# top_level.net
KiCad netlist of a schematic drawn in Altium Designer
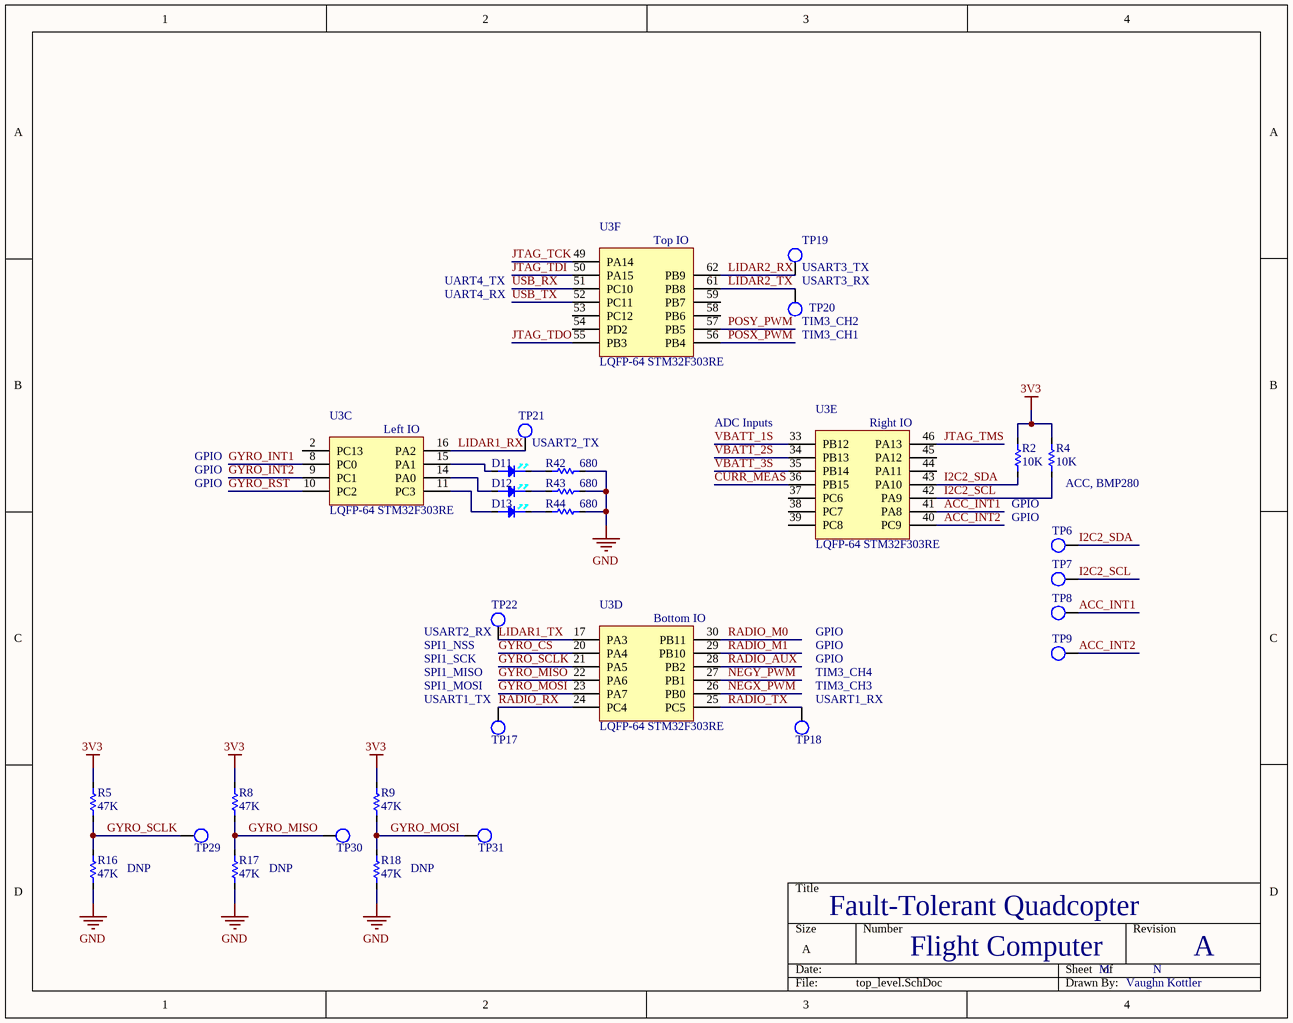
[diagram p0: top_level.SchDoc]

(export (version "E")
  (design (tool "Eeschema 10.0.6"))
  (components
    (comp (ref "D11")
      (value "LED-WHT-20mA")
      (footprint "LED-0805")
      (description "2.2V, 0805")
      (libsource (lib "passive") (part "LED-WHT-20mA"))
    )
    (comp (ref "D12")
      (value "LED-WHT-20mA")
      (footprint "LED-0805")
      (description "2.2V, 0805")
      (libsource (lib "passive") (part "LED-WHT-20mA"))
    )
    (comp (ref "D13")
      (value "LED-WHT-20mA")
      (footprint "LED-0805")
      (description "2.2V, 0805")
      (libsource (lib "passive") (part "LED-WHT-20mA"))
    )
    (comp (ref "R2")
      (value "10K")
      (footprint "RES-0805")
      (description "0805")
      (libsource (lib "passive") (part "RES-10K-1/8W"))
    )
    (comp (ref "R4")
      (value "10K")
      (footprint "RES-0805")
      (description "0805")
      (libsource (lib "passive") (part "RES-10K-1/8W"))
    )
    (comp (ref "R5")
      (value "47K")
      (footprint "RES-0805")
      (description "0805")
      (libsource (lib "passive") (part "RES-47K-1/8W"))
    )
    (comp (ref "R8")
      (value "47K")
      (footprint "RES-0805")
      (description "0805")
      (libsource (lib "passive") (part "RES-47K-1/8W"))
    )
    (comp (ref "R9")
      (value "47K")
      (footprint "RES-0805")
      (description "0805")
      (libsource (lib "passive") (part "RES-47K-1/8W"))
    )
    (comp (ref "R16")
      (value "47K")
      (footprint "RES-0805")
      (description "0805")
      (libsource (lib "passive") (part "RES-47K-1/8W"))
    )
    (comp (ref "R17")
      (value "47K")
      (footprint "RES-0805")
      (description "0805")
      (libsource (lib "passive") (part "RES-47K-1/8W"))
    )
    (comp (ref "R18")
      (value "47K")
      (footprint "RES-0805")
      (description "0805")
      (libsource (lib "passive") (part "RES-47K-1/8W"))
    )
    (comp (ref "R42")
      (value "680")
      (footprint "RES-0805")
      (description "0805")
      (libsource (lib "passive") (part "RES-680-1/8W"))
    )
    (comp (ref "R43")
      (value "680")
      (footprint "RES-0805")
      (description "0805")
      (libsource (lib "passive") (part "RES-680-1/8W"))
    )
    (comp (ref "R44")
      (value "680")
      (footprint "RES-0805")
      (description "0805")
      (libsource (lib "passive") (part "RES-680-1/8W"))
    )
    (comp (ref "TP6")
      (value "Test Point")
      (footprint "0603 Test Point")
      (description "0603")
      (libsource (lib "passive") (part "Test Point"))
    )
    (comp (ref "TP7")
      (value "Test Point")
      (footprint "0603 Test Point")
      (description "0603")
      (libsource (lib "passive") (part "Test Point"))
    )
    (comp (ref "TP8")
      (value "Test Point")
      (footprint "0603 Test Point")
      (description "0603")
      (libsource (lib "passive") (part "Test Point"))
    )
    (comp (ref "TP9")
      (value "Test Point")
      (footprint "0603 Test Point")
      (description "0603")
      (libsource (lib "passive") (part "Test Point"))
    )
    (comp (ref "TP17")
      (value "Test Point")
      (footprint "0603 Test Point")
      (description "0603")
      (libsource (lib "passive") (part "Test Point"))
    )
    (comp (ref "TP18")
      (value "Test Point")
      (footprint "0603 Test Point")
      (description "0603")
      (libsource (lib "passive") (part "Test Point"))
    )
    (comp (ref "TP19")
      (value "Test Point")
      (footprint "0603 Test Point")
      (description "0603")
      (libsource (lib "passive") (part "Test Point"))
    )
    (comp (ref "TP20")
      (value "Test Point")
      (footprint "0603 Test Point")
      (description "0603")
      (libsource (lib "passive") (part "Test Point"))
    )
    (comp (ref "TP21")
      (value "Test Point")
      (footprint "0603 Test Point")
      (description "0603")
      (libsource (lib "passive") (part "Test Point"))
    )
    (comp (ref "TP22")
      (value "Test Point")
      (footprint "0603 Test Point")
      (description "0603")
      (libsource (lib "passive") (part "Test Point"))
    )
    (comp (ref "TP29")
      (value "Test Point")
      (footprint "0603 Test Point")
      (description "0603")
      (libsource (lib "passive") (part "Test Point"))
    )
    (comp (ref "TP30")
      (value "Test Point")
      (footprint "0603 Test Point")
      (description "0603")
      (libsource (lib "passive") (part "Test Point"))
    )
    (comp (ref "TP31")
      (value "Test Point")
      (footprint "0603 Test Point")
      (description "0603")
      (libsource (lib "passive") (part "Test Point"))
    )
    (comp (ref "U3")
      (value "LQFP-64 STM32F303RE")
      (footprint "LQFP64")
      (description "ARM Cortex-M4 32-bit MCU+FPU")
      (libsource (lib "ic") (part "STM32F303RET6"))
    )
  )
  (nets
    (net (code "1") (name "/ACC_INT1") (class "Default")
      (node (ref "TP8") (pin "1") (pinfunction "1_1") (pintype "passive"))
      (node (ref "U3") (pin "41") (pinfunction "PA8_41") (pintype "passive"))
    )
    (net (code "2") (name "/ACC_INT2") (class "Default")
      (node (ref "TP9") (pin "1") (pinfunction "1_1") (pintype "passive"))
      (node (ref "U3") (pin "40") (pinfunction "PC9_40") (pintype "passive"))
    )
    (net (code "3") (name "/CURR_MEAS") (class "Default")
      (node (ref "U3") (pin "36") (pinfunction "PB15_36") (pintype "passive"))
    )
    (net (code "4") (name "/GYRO_CS") (class "Default")
      (node (ref "U3") (pin "20") (pinfunction "PA4_20") (pintype "passive"))
    )
    (net (code "5") (name "/GYRO_INT1") (class "Default")
      (node (ref "U3") (pin "8") (pinfunction "PC0_8") (pintype "passive"))
    )
    (net (code "6") (name "/GYRO_INT2") (class "Default")
      (node (ref "U3") (pin "9") (pinfunction "PC1_9") (pintype "passive"))
    )
    (net (code "7") (name "/GYRO_MISO") (class "Default")
      (node (ref "R17") (pin "2") (pinfunction "2_2") (pintype "passive"))
      (node (ref "R8") (pin "1") (pinfunction "1_1") (pintype "passive"))
      (node (ref "TP30") (pin "1") (pinfunction "1_1") (pintype "passive"))
      (node (ref "U3") (pin "22") (pinfunction "PA6_22") (pintype "passive"))
    )
    (net (code "8") (name "/GYRO_MOSI") (class "Default")
      (node (ref "R18") (pin "2") (pinfunction "2_2") (pintype "passive"))
      (node (ref "R9") (pin "1") (pinfunction "1_1") (pintype "passive"))
      (node (ref "TP31") (pin "1") (pinfunction "1_1") (pintype "passive"))
      (node (ref "U3") (pin "23") (pinfunction "PA7_23") (pintype "passive"))
    )
    (net (code "9") (name "/GYRO_RST") (class "Default")
      (node (ref "U3") (pin "10") (pinfunction "PC2_10") (pintype "passive"))
    )
    (net (code "10") (name "/GYRO_SCLK") (class "Default")
      (node (ref "R16") (pin "2") (pinfunction "2_2") (pintype "passive"))
      (node (ref "R5") (pin "1") (pinfunction "1_1") (pintype "passive"))
      (node (ref "TP29") (pin "1") (pinfunction "1_1") (pintype "passive"))
      (node (ref "U3") (pin "21") (pinfunction "PA5_21") (pintype "passive"))
    )
    (net (code "11") (name "/I2C2_SCL") (class "Default")
      (node (ref "R4") (pin "1") (pinfunction "1_1") (pintype "passive"))
      (node (ref "TP7") (pin "1") (pinfunction "1_1") (pintype "passive"))
      (node (ref "U3") (pin "42") (pinfunction "PA9_42") (pintype "passive"))
    )
    (net (code "12") (name "/I2C2_SDA") (class "Default")
      (node (ref "R2") (pin "1") (pinfunction "1_1") (pintype "passive"))
      (node (ref "TP6") (pin "1") (pinfunction "1_1") (pintype "passive"))
      (node (ref "U3") (pin "43") (pinfunction "PA10_43") (pintype "passive"))
    )
    (net (code "13") (name "/JTAG_TCK") (class "Default")
      (node (ref "U3") (pin "49") (pinfunction "PA14_49") (pintype "passive"))
    )
    (net (code "14") (name "/JTAG_TDI") (class "Default")
      (node (ref "U3") (pin "50") (pinfunction "PA15_50") (pintype "passive"))
    )
    (net (code "15") (name "/JTAG_TDO") (class "Default")
      (node (ref "U3") (pin "55") (pinfunction "PB3_55") (pintype "passive"))
    )
    (net (code "16") (name "/JTAG_TMS") (class "Default")
      (node (ref "U3") (pin "46") (pinfunction "PA13_46") (pintype "passive"))
    )
    (net (code "17") (name "/LIDAR1_RX") (class "Default")
      (node (ref "TP21") (pin "1") (pinfunction "1_1") (pintype "passive"))
      (node (ref "U3") (pin "16") (pinfunction "PA2_16") (pintype "passive"))
    )
    (net (code "18") (name "/LIDAR1_TX") (class "Default")
      (node (ref "TP22") (pin "1") (pinfunction "1_1") (pintype "passive"))
      (node (ref "U3") (pin "17") (pinfunction "PA3_17") (pintype "passive"))
    )
    (net (code "19") (name "/LIDAR2_RX") (class "Default")
      (node (ref "TP19") (pin "1") (pinfunction "1_1") (pintype "passive"))
      (node (ref "U3") (pin "62") (pinfunction "PB9_62") (pintype "passive"))
    )
    (net (code "20") (name "/LIDAR2_TX") (class "Default")
      (node (ref "TP20") (pin "1") (pinfunction "1_1") (pintype "passive"))
      (node (ref "U3") (pin "61") (pinfunction "PB8_61") (pintype "passive"))
    )
    (net (code "21") (name "/NEGX_PWM") (class "Default")
      (node (ref "U3") (pin "26") (pinfunction "PB0_26") (pintype "passive"))
    )
    (net (code "22") (name "/NEGY_PWM") (class "Default")
      (node (ref "U3") (pin "27") (pinfunction "PB1_27") (pintype "passive"))
    )
    (net (code "23") (name "/POSX_PWM") (class "Default")
      (node (ref "U3") (pin "56") (pinfunction "PB4_56") (pintype "passive"))
    )
    (net (code "24") (name "/POSY_PWM") (class "Default")
      (node (ref "U3") (pin "57") (pinfunction "PB5_57") (pintype "passive"))
    )
    (net (code "25") (name "/RADIO_AUX") (class "Default")
      (node (ref "U3") (pin "28") (pinfunction "PB2_28") (pintype "passive"))
    )
    (net (code "26") (name "/RADIO_M0") (class "Default")
      (node (ref "U3") (pin "30") (pinfunction "PB11_30") (pintype "passive"))
    )
    (net (code "27") (name "/RADIO_M1") (class "Default")
      (node (ref "U3") (pin "29") (pinfunction "PB10_29") (pintype "passive"))
    )
    (net (code "28") (name "/RADIO_RX") (class "Default")
      (node (ref "TP17") (pin "1") (pinfunction "1_1") (pintype "passive"))
      (node (ref "U3") (pin "24") (pinfunction "PC4_24") (pintype "passive"))
    )
    (net (code "29") (name "/RADIO_TX") (class "Default")
      (node (ref "TP18") (pin "1") (pinfunction "1_1") (pintype "passive"))
      (node (ref "U3") (pin "25") (pinfunction "PC5_25") (pintype "passive"))
    )
    (net (code "30") (name "/USB_RX") (class "Default")
      (node (ref "U3") (pin "51") (pinfunction "PC10_51") (pintype "passive"))
    )
    (net (code "31") (name "/USB_TX") (class "Default")
      (node (ref "U3") (pin "52") (pinfunction "PC11_52") (pintype "passive"))
    )
    (net (code "32") (name "/VBATT_1S") (class "Default")
      (node (ref "U3") (pin "33") (pinfunction "PB12_33") (pintype "passive"))
    )
    (net (code "33") (name "/VBATT_2S") (class "Default")
      (node (ref "U3") (pin "34") (pinfunction "PB13_34") (pintype "passive"))
    )
    (net (code "34") (name "/VBATT_3S") (class "Default")
      (node (ref "U3") (pin "35") (pinfunction "PB14_35") (pintype "passive"))
    )
    (net (code "35") (name "3V3") (class "Default")
      (node (ref "R2") (pin "2") (pinfunction "2_2") (pintype "passive"))
      (node (ref "R4") (pin "2") (pinfunction "2_2") (pintype "passive"))
      (node (ref "R5") (pin "2") (pinfunction "2_2") (pintype "passive"))
      (node (ref "R8") (pin "2") (pinfunction "2_2") (pintype "passive"))
      (node (ref "R9") (pin "2") (pinfunction "2_2") (pintype "passive"))
    )
    (net (code "36") (name "GND") (class "Default")
      (node (ref "R16") (pin "1") (pinfunction "1_1") (pintype "passive"))
      (node (ref "R17") (pin "1") (pinfunction "1_1") (pintype "passive"))
      (node (ref "R18") (pin "1") (pinfunction "1_1") (pintype "passive"))
      (node (ref "R42") (pin "2") (pinfunction "2_2") (pintype "passive"))
      (node (ref "R43") (pin "2") (pinfunction "2_2") (pintype "passive"))
      (node (ref "R44") (pin "2") (pinfunction "2_2") (pintype "passive"))
    )
    (net (code "37") (name "Net-(D11-AN)") (class "Default")
      (node (ref "D11") (pin "2") (pinfunction "AN_2") (pintype "passive"))
      (node (ref "R42") (pin "1") (pinfunction "1_1") (pintype "passive"))
    )
    (net (code "38") (name "Net-(D11-CT)") (class "Default")
      (node (ref "D11") (pin "1") (pinfunction "CT_1") (pintype "passive"))
      (node (ref "U3") (pin "15") (pinfunction "PA1_15") (pintype "passive"))
    )
    (net (code "39") (name "Net-(D12-AN)") (class "Default")
      (node (ref "D12") (pin "2") (pinfunction "AN_2") (pintype "passive"))
      (node (ref "R43") (pin "1") (pinfunction "1_1") (pintype "passive"))
    )
    (net (code "40") (name "Net-(D12-CT)") (class "Default")
      (node (ref "D12") (pin "1") (pinfunction "CT_1") (pintype "passive"))
      (node (ref "U3") (pin "14") (pinfunction "PA0_14") (pintype "passive"))
    )
    (net (code "41") (name "Net-(D13-AN)") (class "Default")
      (node (ref "D13") (pin "2") (pinfunction "AN_2") (pintype "passive"))
      (node (ref "R44") (pin "1") (pinfunction "1_1") (pintype "passive"))
    )
    (net (code "42") (name "Net-(D13-CT)") (class "Default")
      (node (ref "D13") (pin "1") (pinfunction "CT_1") (pintype "passive"))
      (node (ref "U3") (pin "11") (pinfunction "PC3_11") (pintype "passive"))
    )
    (net (code "43") (name "unconnected-(U3C-PC13-Pad2)") (class "Default")
      (node (ref "U3") (pin "2") (pinfunction "PC13_2") (pintype "passive"))
    )
    (net (code "44") (name "unconnected-(U3E-PA11-Pad44)") (class "Default")
      (node (ref "U3") (pin "44") (pinfunction "PA11_44") (pintype "passive"))
    )
    (net (code "45") (name "unconnected-(U3E-PA12-Pad45)") (class "Default")
      (node (ref "U3") (pin "45") (pinfunction "PA12_45") (pintype "passive"))
    )
    (net (code "46") (name "unconnected-(U3E-PC6-Pad37)") (class "Default")
      (node (ref "U3") (pin "37") (pinfunction "PC6_37") (pintype "passive"))
    )
    (net (code "47") (name "unconnected-(U3E-PC7-Pad38)") (class "Default")
      (node (ref "U3") (pin "38") (pinfunction "PC7_38") (pintype "passive"))
    )
    (net (code "48") (name "unconnected-(U3E-PC8-Pad39)") (class "Default")
      (node (ref "U3") (pin "39") (pinfunction "PC8_39") (pintype "passive"))
    )
    (net (code "49") (name "unconnected-(U3F-PB6-Pad58)") (class "Default")
      (node (ref "U3") (pin "58") (pinfunction "PB6_58") (pintype "passive"))
    )
    (net (code "50") (name "unconnected-(U3F-PB7-Pad59)") (class "Default")
      (node (ref "U3") (pin "59") (pinfunction "PB7_59") (pintype "passive"))
    )
    (net (code "51") (name "unconnected-(U3F-PC12-Pad53)") (class "Default")
      (node (ref "U3") (pin "53") (pinfunction "PC12_53") (pintype "passive"))
    )
    (net (code "52") (name "unconnected-(U3F-PD2-Pad54)") (class "Default")
      (node (ref "U3") (pin "54") (pinfunction "PD2_54") (pintype "passive"))
    )
  )
)
